# Schematic_Altium.net
KiCad netlist of a schematic drawn in Altium Designer
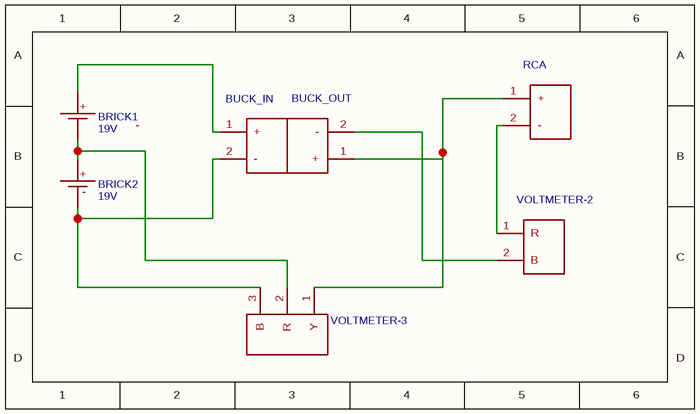
[diagram p0: Schematic (Altium).schdoc]

(export (version "E")
  (design (tool "Eeschema 10.0.6"))
  (components
    (comp (ref "BRICK1")
      (value "19V")
      (fields (field (name "CONTRIBUTOR") "adrejia"))
      (libsource (lib "altium-import") (part "root_3_19V_"))
    )
    (comp (ref "BRICK2")
      (value "19V")
      (fields (field (name "CONTRIBUTOR") "adrejia"))
      (libsource (lib "altium-import") (part "root_3_19V_"))
    )
    (comp (ref "BUCK_IN")
      (value "MKDSN1.5/2-5.08")
      (fields
        (field (name "MANUFACTURER") "Phoenix Contact(菲尼克斯)")
        (field (name "MANUFACTURER PART") "1729128")
      )
      (libsource (lib "altium-import") (part "root_0_MKDSN1.5/2-5.08_"))
    )
    (comp (ref "BUCK_OUT")
      (value "MKDSN1.5/2-5.08")
      (fields
        (field (name "MANUFACTURER") "Phoenix Contact(菲尼克斯)")
        (field (name "MANUFACTURER PART") "1729128")
      )
      (libsource (lib "altium-import") (part "root_2_MKDSN1.5/2-5.08_"))
    )
    (comp (ref "RCA")
      (value "MKDSN1.5/2-5.08")
      (fields
        (field (name "MANUFACTURER") "Phoenix Contact(菲尼克斯)")
        (field (name "MANUFACTURER PART") "1729128")
      )
      (libsource (lib "altium-import") (part "root_0_MKDSN1.5/2-5.08_"))
    )
    (comp (ref "VOLTMETER-2")
      (value "MKDSN1.5/2-5.08")
      (fields
        (field (name "MANUFACTURER") "Phoenix Contact(菲尼克斯)")
        (field (name "MANUFACTURER PART") "1729128")
      )
      (libsource (lib "altium-import") (part "root_0_MKDSN1.5/2-5.08_"))
    )
    (comp (ref "VOLTMETER-3")
      (value "MKDSN1.5/3-5.08")
      (fields
        (field (name "MANUFACTURER") "Phoenix Contact(菲尼克斯)")
        (field (name "MANUFACTURER PART") "1729131")
      )
      (libsource (lib "altium-import") (part "root_3_MKDSN1.5/3-5.08_"))
    )
  )
  (nets
    (net (code "1") (name "Net-(BRICK1-+)") (class "Default")
      (node (ref "BRICK1") (pin "1") (pinfunction "+_1") (pintype "passive"))
      (node (ref "BUCK_IN") (pin "1") (pinfunction "+_1") (pintype "passive"))
    )
    (net (code "2") (name "Net-(BRICK1--)") (class "Default")
      (node (ref "BRICK1") (pin "2") (pinfunction "-_2") (pintype "passive"))
      (node (ref "BRICK2") (pin "1") (pinfunction "+_1") (pintype "passive"))
      (node (ref "VOLTMETER-3") (pin "2") (pinfunction "R_2") (pintype "passive"))
    )
    (net (code "3") (name "Net-(BRICK2--)") (class "Default")
      (node (ref "BRICK2") (pin "2") (pinfunction "-_2") (pintype "passive"))
      (node (ref "BUCK_IN") (pin "2") (pinfunction "-_2") (pintype "passive"))
      (node (ref "VOLTMETER-3") (pin "3") (pinfunction "B_3") (pintype "passive"))
    )
    (net (code "4") (name "Net-(BUCK_OUT-+)") (class "Default")
      (node (ref "BUCK_OUT") (pin "1") (pinfunction "+_1") (pintype "passive"))
      (node (ref "RCA") (pin "1") (pinfunction "+_1") (pintype "passive"))
      (node (ref "VOLTMETER-3") (pin "1") (pinfunction "Y_1") (pintype "passive"))
    )
    (net (code "5") (name "Net-(BUCK_OUT--)") (class "Default")
      (node (ref "BUCK_OUT") (pin "2") (pinfunction "-_2") (pintype "passive"))
      (node (ref "VOLTMETER-2") (pin "2") (pinfunction "-_2") (pintype "passive"))
    )
    (net (code "6") (name "Net-(RCA--)") (class "Default")
      (node (ref "RCA") (pin "2") (pinfunction "-_2") (pintype "passive"))
      (node (ref "VOLTMETER-2") (pin "1") (pinfunction "+_1") (pintype "passive"))
    )
  )
)
